# mcp1642b.net
KiCad netlist of a schematic drawn in EAGLE
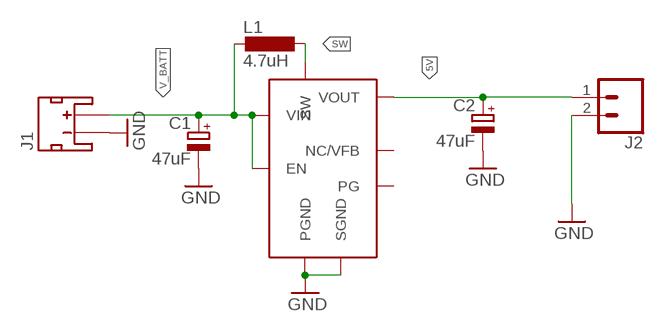
[diagram p0: schematic, sheet 1]

(export (version "E")
  (design (tool "Eeschema 10.0.6"))
  (components
    (comp (ref "C1")
      (value "47uF")
      (footprint "eagle-import:153CLV-0505")
      (libsource (lib "eagle-import") (part "CPOL-EU153CLV-0505"))
    )
    (comp (ref "C2")
      (value "47uF")
      (footprint "eagle-import:153CLV-0505")
      (libsource (lib "eagle-import") (part "CPOL-EU153CLV-0505"))
    )
    (comp (ref "J1")
      (value "JST_2MM_MALE")
      (footprint "eagle-import:JST-2-SMD")
      (libsource (lib "eagle-import") (part "JST_2MM_MALE"))
    )
    (comp (ref "J2")
      (value "CONN_02PTH4")
      (footprint "eagle-import:1X02_XTRA_BIG")
      (libsource (lib "eagle-import") (part "CONN_02PTH4"))
    )
    (comp (ref "L1")
      (value "4.7uH")
      (footprint "eagle-import:POWER-CHOKE_WE-TPC")
      (libsource (lib "eagle-import") (part "L-EUWE-TPC"))
    )
    (comp (ref "U11")
      (value "MCP1642B")
      (footprint "eagle-import:MCP1642B")
      (libsource (lib "eagle-import") (part "MCP1642B"))
    )
  )
  (nets
    (net (code "1") (name "5V") (class "Default")
      (node (ref "C2") (pin "+") (pinfunction "+_+") (pintype "passive"))
      (node (ref "J2") (pin "1") (pinfunction "1_1") (pintype "passive"))
      (node (ref "U11") (pin "VOUT") (pinfunction "VOUT_VOUT") (pintype "bidirectional"))
    )
    (net (code "2") (name "GND") (class "Default")
      (node (ref "C1") (pin "-") (pinfunction "-_-") (pintype "passive"))
      (node (ref "C2") (pin "-") (pinfunction "-_-") (pintype "passive"))
      (node (ref "J1") (pin "1") (pinfunction "-_1") (pintype "bidirectional"))
      (node (ref "J2") (pin "2") (pinfunction "2_2") (pintype "passive"))
      (node (ref "U11") (pin "PGND") (pinfunction "PGND_PGND") (pintype "bidirectional"))
      (node (ref "U11") (pin "SGND") (pinfunction "SGND_SGND") (pintype "bidirectional"))
    )
    (net (code "3") (name "SW") (class "Default")
      (node (ref "L1") (pin "1") (pinfunction "1_1") (pintype "passive"))
      (node (ref "U11") (pin "SW") (pinfunction "SW_SW") (pintype "bidirectional"))
    )
    (net (code "4") (name "V_BATT") (class "Default")
      (node (ref "C1") (pin "+") (pinfunction "+_+") (pintype "passive"))
      (node (ref "J1") (pin "2") (pinfunction "+_2") (pintype "bidirectional"))
      (node (ref "L1") (pin "2") (pinfunction "2_2") (pintype "passive"))
      (node (ref "U11") (pin "EN") (pinfunction "EN_EN") (pintype "bidirectional"))
      (node (ref "U11") (pin "VIN") (pinfunction "VIN_VIN") (pintype "bidirectional"))
    )
    (net (code "5") (name "unconnected-(J1-PAD1-PadNC1)") (class "Default")
      (node (ref "J1") (pin "NC1") (pinfunction "PAD1_NC1") (pintype "bidirectional"))
    )
    (net (code "6") (name "unconnected-(J1-PAD2-PadNC2)") (class "Default")
      (node (ref "J1") (pin "NC2") (pinfunction "PAD2_NC2") (pintype "bidirectional"))
    )
    (net (code "7") (name "unconnected-(U11-NC{slash}VFB-PadNC)") (class "Default")
      (node (ref "U11") (pin "NC") (pinfunction "NC/VFB_NC") (pintype "bidirectional"))
    )
    (net (code "8") (name "unconnected-(U11-PadPG)") (class "Default")
      (node (ref "U11") (pin "PG") (pinfunction "PG_PG") (pintype "bidirectional"))
    )
  )
)
